# EXPAND.net
KiCad netlist of a schematic drawn in EAGLE
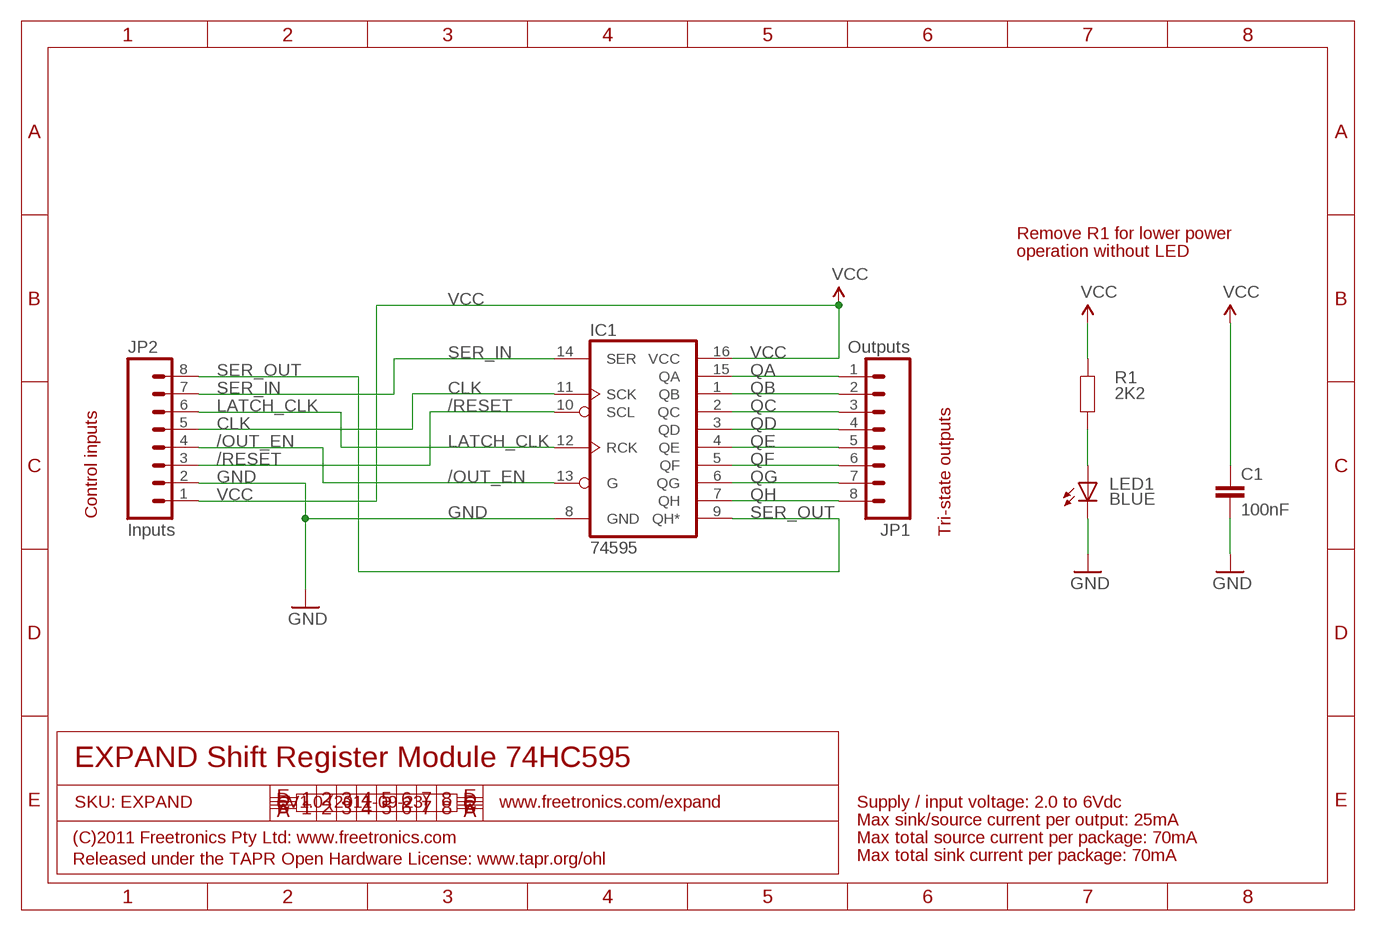
[diagram p0: schematic, sheet 1]

(export (version "E")
  (design (tool "Eeschema 10.0.6"))
  (components
    (comp (ref "C1")
      (value "100nF")
      (footprint "eagle-import:0603")
      (libsource (lib "eagle-import") (part "CAP0603"))
    )
    (comp (ref "IC1")
      (value "74595")
      (footprint "eagle-import:TSSOP16")
      (libsource (lib "eagle-import") (part "74595"))
    )
    (comp (ref "JP1")
      (value "Outputs")
      (footprint "eagle-import:1X08")
      (libsource (lib "eagle-import") (part "M08"))
    )
    (comp (ref "JP2")
      (value "Inputs")
      (footprint "eagle-import:1X08")
      (libsource (lib "eagle-import") (part "M08"))
    )
    (comp (ref "LED1")
      (value "BLUE")
      (footprint "eagle-import:LED-0603")
      (libsource (lib "eagle-import") (part "LED0603"))
    )
    (comp (ref "R1")
      (value "2K2")
      (footprint "eagle-import:0603")
      (libsource (lib "eagle-import") (part "RESISTOR0603"))
    )
  )
  (nets
    (net (code "1") (name "/CLK") (class "Default")
      (node (ref "IC1") (pin "11") (pinfunction "SCK_11") (pintype "input"))
      (node (ref "JP2") (pin "5") (pinfunction "5_5") (pintype "passive"))
    )
    (net (code "2") (name "/LATCH_CLK") (class "Default")
      (node (ref "IC1") (pin "12") (pinfunction "RCK_12") (pintype "input"))
      (node (ref "JP2") (pin "6") (pinfunction "6_6") (pintype "passive"))
    )
    (net (code "3") (name "/QA") (class "Default")
      (node (ref "IC1") (pin "15") (pinfunction "QA_15") (pintype "tri_state"))
      (node (ref "JP1") (pin "1") (pinfunction "1_1") (pintype "passive"))
    )
    (net (code "4") (name "/QB") (class "Default")
      (node (ref "IC1") (pin "1") (pinfunction "QB_1") (pintype "tri_state"))
      (node (ref "JP1") (pin "2") (pinfunction "2_2") (pintype "passive"))
    )
    (net (code "5") (name "/QC") (class "Default")
      (node (ref "IC1") (pin "2") (pinfunction "QC_2") (pintype "tri_state"))
      (node (ref "JP1") (pin "3") (pinfunction "3_3") (pintype "passive"))
    )
    (net (code "6") (name "/QD") (class "Default")
      (node (ref "IC1") (pin "3") (pinfunction "QD_3") (pintype "tri_state"))
      (node (ref "JP1") (pin "4") (pinfunction "4_4") (pintype "passive"))
    )
    (net (code "7") (name "/QE") (class "Default")
      (node (ref "IC1") (pin "4") (pinfunction "QE_4") (pintype "tri_state"))
      (node (ref "JP1") (pin "5") (pinfunction "5_5") (pintype "passive"))
    )
    (net (code "8") (name "/QF") (class "Default")
      (node (ref "IC1") (pin "5") (pinfunction "QF_5") (pintype "tri_state"))
      (node (ref "JP1") (pin "6") (pinfunction "6_6") (pintype "passive"))
    )
    (net (code "9") (name "/QG") (class "Default")
      (node (ref "IC1") (pin "6") (pinfunction "QG_6") (pintype "tri_state"))
      (node (ref "JP1") (pin "7") (pinfunction "7_7") (pintype "passive"))
    )
    (net (code "10") (name "/QH") (class "Default")
      (node (ref "IC1") (pin "7") (pinfunction "QH_7") (pintype "tri_state"))
      (node (ref "JP1") (pin "8") (pinfunction "8_8") (pintype "passive"))
    )
    (net (code "11") (name "/SER_IN") (class "Default")
      (node (ref "IC1") (pin "14") (pinfunction "SER_14") (pintype "input"))
      (node (ref "JP2") (pin "7") (pinfunction "7_7") (pintype "passive"))
    )
    (net (code "12") (name "/SER_OUT") (class "Default")
      (node (ref "IC1") (pin "9") (pinfunction "QH*_9") (pintype "tri_state"))
      (node (ref "JP2") (pin "8") (pinfunction "8_8") (pintype "passive"))
    )
    (net (code "13") (name "/{slash}OUT_EN") (class "Default")
      (node (ref "IC1") (pin "13") (pinfunction "G_13") (pintype "input"))
      (node (ref "JP2") (pin "4") (pinfunction "4_4") (pintype "passive"))
    )
    (net (code "14") (name "/{slash}RESET") (class "Default")
      (node (ref "IC1") (pin "10") (pinfunction "SCL_10") (pintype "input"))
      (node (ref "JP2") (pin "3") (pinfunction "3_3") (pintype "passive"))
    )
    (net (code "15") (name "GND") (class "Default")
      (node (ref "C1") (pin "2") (pinfunction "2_2") (pintype "passive"))
      (node (ref "IC1") (pin "8") (pinfunction "GND_8") (pintype "power_in"))
      (node (ref "JP2") (pin "2") (pinfunction "2_2") (pintype "passive"))
      (node (ref "LED1") (pin "C") (pinfunction "C_C") (pintype "passive"))
    )
    (net (code "16") (name "Net-(LED1-PadA)") (class "Default")
      (node (ref "LED1") (pin "A") (pinfunction "A_A") (pintype "passive"))
      (node (ref "R1") (pin "1") (pinfunction "1_1") (pintype "passive"))
    )
    (net (code "17") (name "VCC") (class "Default")
      (node (ref "C1") (pin "1") (pinfunction "1_1") (pintype "passive"))
      (node (ref "IC1") (pin "16") (pinfunction "VCC_16") (pintype "power_in"))
      (node (ref "JP2") (pin "1") (pinfunction "1_1") (pintype "passive"))
      (node (ref "R1") (pin "2") (pinfunction "2_2") (pintype "passive"))
    )
  )
)
